# NRF51822.net
KiCad netlist of a schematic drawn in Altium Designer
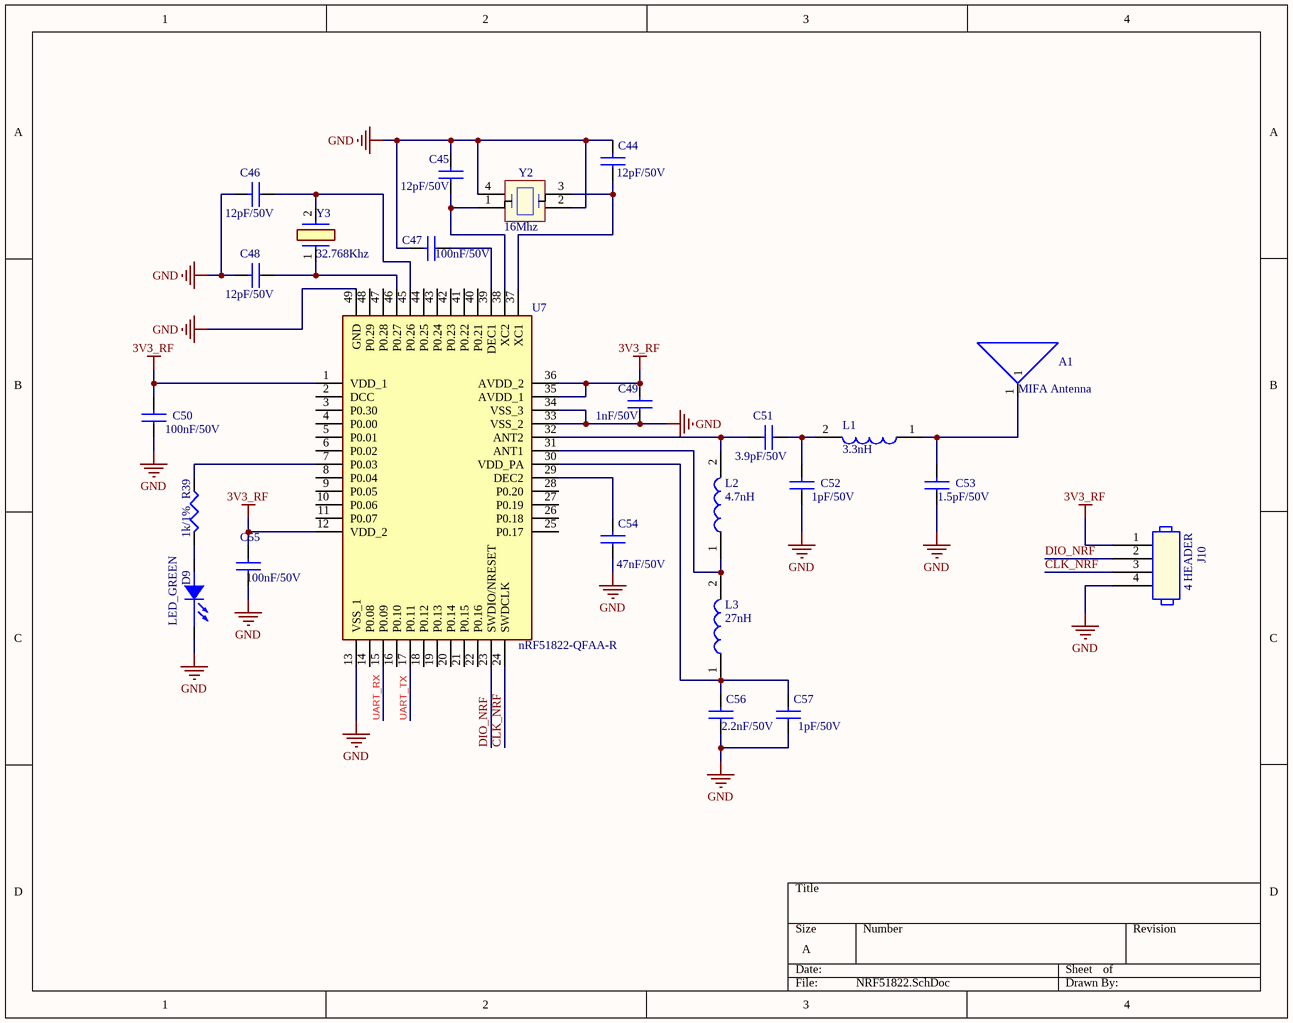
[diagram p0: NRF51822.SchDoc]

(export (version "E")
  (design (tool "Eeschema 10.0.6"))
  (components
    (comp (ref "A1")
      (value "MIFA Antenna")
      (footprint "ANT-2.4GHZ-8.0X1.0MM")
      (description "None")
      (libsource (lib "VESC_DEVICE_Library") (part "Ceramic _ANTENNA"))
    )
    (comp (ref "C44") (value "12pF/50V") (footprint "C0402") (libsource (lib "*") (part "CAP NP")))
    (comp (ref "C45") (value "12pF/50V") (footprint "C0402") (libsource (lib "*") (part "CAP NP")))
    (comp (ref "C46") (value "12pF/50V") (footprint "C0402") (libsource (lib "*") (part "CAP NP")))
    (comp (ref "C47") (value "100nF/50V") (footprint "C0402") (libsource (lib "*") (part "CAP NP")))
    (comp (ref "C48") (value "12pF/50V") (footprint "C0402") (libsource (lib "*") (part "CAP NP")))
    (comp (ref "C49") (value "1nF/50V") (footprint "C0402") (libsource (lib "*") (part "CAP NP")))
    (comp (ref "C50") (value "100nF/50V") (footprint "C0402") (libsource (lib "*") (part "CAP NP")))
    (comp (ref "C51") (value "3.9pF/50V") (footprint "C0402") (libsource (lib "*") (part "CAP NP")))
    (comp (ref "C52") (value "1pF/50V") (footprint "C0402") (libsource (lib "*") (part "CAP NP")))
    (comp (ref "C53") (value "1.5pF/50V") (footprint "C0402") (libsource (lib "*") (part "CAP NP")))
    (comp (ref "C54") (value "47nF/50V") (footprint "C0402") (libsource (lib "*") (part "CAP NP")))
    (comp (ref "C55") (value "100nF/50V") (footprint "C0402") (libsource (lib "*") (part "CAP NP")))
    (comp (ref "C56") (value "2.2nF/50V") (footprint "C0402") (libsource (lib "*") (part "CAP NP")))
    (comp (ref "C57") (value "1pF/50V") (footprint "C0402") (libsource (lib "*") (part "CAP NP")))
    (comp (ref "D9") (value "LED_GREEN") (footprint "LED0603") (libsource (lib "*") (part "LED")))
    (comp (ref "J10") (value "4 HEADER") (footprint "ISP-4P-2_54") (libsource (lib "*") (part "4 HEADER")))
    (comp (ref "L1")
      (value "3.3nH")
      (footprint "LQG15WH0N7B02D")
      (description "Inductor")
      (fields
        (field (name "MANUFACTURER_PART_NUMBER") "LQG15HS4N7C02D")
        (field (name "MOUSER PART NUMBER") "81-LQG15HS4N7C02D")
      )
      (libsource (lib "VESC_DEVICE_Library") (part "LQG15HS4N7C02D"))
    )
    (comp (ref "L2")
      (value "4.7nH")
      (footprint "LQG15WH0N7B02D")
      (description "Inductor")
      (fields
        (field (name "MANUFACTURER_PART_NUMBER") "LQG15HS4N7C02D")
        (field (name "MOUSER PART NUMBER") "81-LQG15HS4N7C02D")
      )
      (libsource (lib "VESC_DEVICE_Library") (part "LQG15HS4N7C02D"))
    )
    (comp (ref "L3")
      (value "27nH")
      (footprint "LQG15WH0N7B02D")
      (description "Inductor")
      (fields
        (field (name "MANUFACTURER_PART_NUMBER") "LQG15HS4N7C02D")
        (field (name "MOUSER PART NUMBER") "81-LQG15HS4N7C02D")
      )
      (libsource (lib "VESC_DEVICE_Library") (part "LQG15HS4N7C02D"))
    )
    (comp (ref "R39") (value "1k/1%") (footprint "R0402") (libsource (lib "*") (part "RESISTOR")))
    (comp (ref "U7")
      (value "nRF51822-QFAA-R")
      (footprint "SamacSys:QFN40P600X600X95-49N-D")
      (description "Integrated Circuit")
      (fields
        (field (name "MOUSER PART NUMBER") "949-NRF51822-QFAA-R")
        (field (name "ARROW PART NUMBER") "NRF51822-QFAA-R")
      )
      (libsource (lib "VESC_DEVICE_Library") (part "nRF51822-QFAA-R"))
    )
    (comp (ref "Y2")
      (value "16Mhz")
      (footprint "Q22FA12800400")
      (description "Crystal or Oscillator")
      (fields (field (name "MANUFACTURER_PART_NUMBER") "Q22FA12800400"))
      (libsource (lib "VESC_DEVICE_Library") (part "Q22FA12800400"))
    )
    (comp (ref "Y3")
      (value "32.768Khz")
      (footprint "ABS0532768KHZ9T")
      (description "Crystal or Oscillator")
      (fields
        (field (name "MANUFACTURER_PART_NUMBER") "ABS05-32.768KHZ-9-T")
        (field (name "MOUSER PART NUMBER") "815-ABS05-32.768K9T")
      )
      (libsource (lib "VESC_DEVICE_Library") (part "ABS05-32.768KHZ-9-T"))
    )
  )
  (nets
    (net (code "1") (name "/CLK_NRF") (class "Default")
      (node (ref "J10") (pin "3") (pinfunction "3_3") (pintype "passive"))
      (node (ref "U7") (pin "24") (pinfunction "SWDCLK_24") (pintype "passive"))
    )
    (net (code "2") (name "/DIO_NRF") (class "Default")
      (node (ref "J10") (pin "2") (pinfunction "2_2") (pintype "passive"))
      (node (ref "U7") (pin "23") (pinfunction "SWDIO/NRESET_23") (pintype "passive"))
    )
    (net (code "3") (name "/UART_RX") (class "Default")
      (node (ref "U7") (pin "15") (pinfunction "P0.09_15") (pintype "passive"))
    )
    (net (code "4") (name "/UART_TX") (class "Default")
      (node (ref "U7") (pin "17") (pinfunction "P0.11_17") (pintype "passive"))
    )
    (net (code "5") (name "3V3_RF") (class "Default")
      (node (ref "C49") (pin "2") (pinfunction "2_2") (pintype "passive"))
      (node (ref "C50") (pin "2") (pinfunction "2_2") (pintype "passive"))
      (node (ref "C55") (pin "2") (pinfunction "2_2") (pintype "passive"))
      (node (ref "J10") (pin "1") (pinfunction "1_1") (pintype "passive"))
      (node (ref "U7") (pin "1") (pinfunction "VDD_1_1") (pintype "passive"))
      (node (ref "U7") (pin "12") (pinfunction "VDD_2_12") (pintype "passive"))
      (node (ref "U7") (pin "35") (pinfunction "AVDD_1_35") (pintype "passive"))
      (node (ref "U7") (pin "36") (pinfunction "AVDD_2_36") (pintype "passive"))
    )
    (net (code "6") (name "GND") (class "Default")
      (node (ref "C44") (pin "2") (pinfunction "2_2") (pintype "passive"))
      (node (ref "C45") (pin "2") (pinfunction "2_2") (pintype "passive"))
      (node (ref "C46") (pin "2") (pinfunction "2_2") (pintype "passive"))
      (node (ref "C47") (pin "2") (pinfunction "2_2") (pintype "passive"))
      (node (ref "C48") (pin "2") (pinfunction "2_2") (pintype "passive"))
      (node (ref "C49") (pin "1") (pinfunction "1_1") (pintype "passive"))
      (node (ref "C50") (pin "1") (pinfunction "1_1") (pintype "passive"))
      (node (ref "C52") (pin "1") (pinfunction "1_1") (pintype "passive"))
      (node (ref "C53") (pin "1") (pinfunction "1_1") (pintype "passive"))
      (node (ref "C54") (pin "1") (pinfunction "1_1") (pintype "passive"))
      (node (ref "C55") (pin "1") (pinfunction "1_1") (pintype "passive"))
      (node (ref "C56") (pin "1") (pinfunction "1_1") (pintype "passive"))
      (node (ref "C57") (pin "1") (pinfunction "1_1") (pintype "passive"))
      (node (ref "D9") (pin "1") (pinfunction "CATHODE_1") (pintype "passive"))
      (node (ref "J10") (pin "4") (pinfunction "4_4") (pintype "passive"))
      (node (ref "U7") (pin "13") (pinfunction "VSS_1_13") (pintype "passive"))
      (node (ref "U7") (pin "33") (pinfunction "VSS_2_33") (pintype "passive"))
      (node (ref "U7") (pin "34") (pinfunction "VSS_3_34") (pintype "passive"))
      (node (ref "U7") (pin "49") (pinfunction "GND_49") (pintype "passive"))
      (node (ref "Y2") (pin "2") (pinfunction "GND_1_2") (pintype "passive"))
      (node (ref "Y2") (pin "4") (pinfunction "GND_2_4") (pintype "passive"))
    )
    (net (code "7") (name "Net-(A1-Pad1)") (class "Default")
      (node (ref "A1") (pin "1") (pinfunction "1_1") (pintype "passive"))
      (node (ref "C53") (pin "2") (pinfunction "2_2") (pintype "passive"))
      (node (ref "L1") (pin "1") (pinfunction "1_1") (pintype "passive"))
    )
    (net (code "8") (name "Net-(C51-Pad1)") (class "Default")
      (node (ref "C51") (pin "1") (pinfunction "1_1") (pintype "passive"))
      (node (ref "C52") (pin "2") (pinfunction "2_2") (pintype "passive"))
      (node (ref "L1") (pin "2") (pinfunction "2_2") (pintype "passive"))
    )
    (net (code "9") (name "Net-(D9-ANODE)") (class "Default")
      (node (ref "D9") (pin "2") (pinfunction "ANODE_2") (pintype "passive"))
      (node (ref "R39") (pin "1") (pinfunction "1_1") (pintype "passive"))
    )
    (net (code "10") (name "Net-(U7-ANT1)") (class "Default")
      (node (ref "L2") (pin "1") (pinfunction "1_1") (pintype "passive"))
      (node (ref "L3") (pin "2") (pinfunction "2_2") (pintype "passive"))
      (node (ref "U7") (pin "31") (pinfunction "ANT1_31") (pintype "passive"))
    )
    (net (code "11") (name "Net-(U7-ANT2)") (class "Default")
      (node (ref "C51") (pin "2") (pinfunction "2_2") (pintype "passive"))
      (node (ref "L2") (pin "2") (pinfunction "2_2") (pintype "passive"))
      (node (ref "U7") (pin "32") (pinfunction "ANT2_32") (pintype "passive"))
    )
    (net (code "12") (name "Net-(U7-DEC1)") (class "Default")
      (node (ref "C47") (pin "1") (pinfunction "1_1") (pintype "passive"))
      (node (ref "U7") (pin "39") (pinfunction "DEC1_39") (pintype "passive"))
    )
    (net (code "13") (name "Net-(U7-DEC2)") (class "Default")
      (node (ref "C54") (pin "2") (pinfunction "2_2") (pintype "passive"))
      (node (ref "U7") (pin "29") (pinfunction "DEC2_29") (pintype "passive"))
    )
    (net (code "14") (name "Net-(U7-P0.03)") (class "Default")
      (node (ref "R39") (pin "2") (pinfunction "2_2") (pintype "passive"))
      (node (ref "U7") (pin "7") (pinfunction "P0.03_7") (pintype "passive"))
    )
    (net (code "15") (name "Net-(U7-P0.26)") (class "Default")
      (node (ref "C46") (pin "1") (pinfunction "1_1") (pintype "passive"))
      (node (ref "U7") (pin "45") (pinfunction "P0.26_45") (pintype "passive"))
      (node (ref "Y3") (pin "2") (pinfunction "2_2") (pintype "passive"))
    )
    (net (code "16") (name "Net-(U7-P0.27)") (class "Default")
      (node (ref "C48") (pin "1") (pinfunction "1_1") (pintype "passive"))
      (node (ref "U7") (pin "46") (pinfunction "P0.27_46") (pintype "passive"))
      (node (ref "Y3") (pin "1") (pinfunction "1_1") (pintype "passive"))
    )
    (net (code "17") (name "Net-(U7-VDD_PA)") (class "Default")
      (node (ref "C56") (pin "2") (pinfunction "2_2") (pintype "passive"))
      (node (ref "C57") (pin "2") (pinfunction "2_2") (pintype "passive"))
      (node (ref "L3") (pin "1") (pinfunction "1_1") (pintype "passive"))
      (node (ref "U7") (pin "30") (pinfunction "VDD_PA_30") (pintype "passive"))
    )
    (net (code "18") (name "Net-(U7-XC1)") (class "Default")
      (node (ref "C44") (pin "1") (pinfunction "1_1") (pintype "passive"))
      (node (ref "U7") (pin "37") (pinfunction "XC1_37") (pintype "passive"))
      (node (ref "Y2") (pin "3") (pinfunction "CRYSTAL_2_3") (pintype "passive"))
    )
    (net (code "19") (name "Net-(U7-XC2)") (class "Default")
      (node (ref "C45") (pin "1") (pinfunction "1_1") (pintype "passive"))
      (node (ref "U7") (pin "38") (pinfunction "XC2_38") (pintype "passive"))
      (node (ref "Y2") (pin "1") (pinfunction "CRYSTAL_1_1") (pintype "passive"))
    )
    (net (code "20") (name "unconnected-(U7-DCC-Pad2)") (class "Default")
      (node (ref "U7") (pin "2") (pinfunction "DCC_2") (pintype "passive"))
    )
    (net (code "21") (name "unconnected-(U7-P0.00-Pad4)") (class "Default")
      (node (ref "U7") (pin "4") (pinfunction "P0.00_4") (pintype "passive"))
    )
    (net (code "22") (name "unconnected-(U7-P0.01-Pad5)") (class "Default")
      (node (ref "U7") (pin "5") (pinfunction "P0.01_5") (pintype "passive"))
    )
    (net (code "23") (name "unconnected-(U7-P0.02-Pad6)") (class "Default")
      (node (ref "U7") (pin "6") (pinfunction "P0.02_6") (pintype "passive"))
    )
    (net (code "24") (name "unconnected-(U7-P0.04-Pad8)") (class "Default")
      (node (ref "U7") (pin "8") (pinfunction "P0.04_8") (pintype "passive"))
    )
    (net (code "25") (name "unconnected-(U7-P0.05-Pad9)") (class "Default")
      (node (ref "U7") (pin "9") (pinfunction "P0.05_9") (pintype "passive"))
    )
    (net (code "26") (name "unconnected-(U7-P0.06-Pad10)") (class "Default")
      (node (ref "U7") (pin "10") (pinfunction "P0.06_10") (pintype "passive"))
    )
    (net (code "27") (name "unconnected-(U7-P0.07-Pad11)") (class "Default")
      (node (ref "U7") (pin "11") (pinfunction "P0.07_11") (pintype "passive"))
    )
    (net (code "28") (name "unconnected-(U7-P0.08-Pad14)") (class "Default")
      (node (ref "U7") (pin "14") (pinfunction "P0.08_14") (pintype "passive"))
    )
    (net (code "29") (name "unconnected-(U7-P0.10-Pad16)") (class "Default")
      (node (ref "U7") (pin "16") (pinfunction "P0.10_16") (pintype "passive"))
    )
    (net (code "30") (name "unconnected-(U7-P0.12-Pad18)") (class "Default")
      (node (ref "U7") (pin "18") (pinfunction "P0.12_18") (pintype "passive"))
    )
    (net (code "31") (name "unconnected-(U7-P0.13-Pad19)") (class "Default")
      (node (ref "U7") (pin "19") (pinfunction "P0.13_19") (pintype "passive"))
    )
    (net (code "32") (name "unconnected-(U7-P0.14-Pad20)") (class "Default")
      (node (ref "U7") (pin "20") (pinfunction "P0.14_20") (pintype "passive"))
    )
    (net (code "33") (name "unconnected-(U7-P0.15-Pad21)") (class "Default")
      (node (ref "U7") (pin "21") (pinfunction "P0.15_21") (pintype "passive"))
    )
    (net (code "34") (name "unconnected-(U7-P0.16-Pad22)") (class "Default")
      (node (ref "U7") (pin "22") (pinfunction "P0.16_22") (pintype "passive"))
    )
    (net (code "35") (name "unconnected-(U7-P0.17-Pad25)") (class "Default")
      (node (ref "U7") (pin "25") (pinfunction "P0.17_25") (pintype "passive"))
    )
    (net (code "36") (name "unconnected-(U7-P0.18-Pad26)") (class "Default")
      (node (ref "U7") (pin "26") (pinfunction "P0.18_26") (pintype "passive"))
    )
    (net (code "37") (name "unconnected-(U7-P0.19-Pad27)") (class "Default")
      (node (ref "U7") (pin "27") (pinfunction "P0.19_27") (pintype "passive"))
    )
    (net (code "38") (name "unconnected-(U7-P0.20-Pad28)") (class "Default")
      (node (ref "U7") (pin "28") (pinfunction "P0.20_28") (pintype "passive"))
    )
    (net (code "39") (name "unconnected-(U7-P0.21-Pad40)") (class "Default")
      (node (ref "U7") (pin "40") (pinfunction "P0.21_40") (pintype "passive"))
    )
    (net (code "40") (name "unconnected-(U7-P0.22-Pad41)") (class "Default")
      (node (ref "U7") (pin "41") (pinfunction "P0.22_41") (pintype "passive"))
    )
    (net (code "41") (name "unconnected-(U7-P0.23-Pad42)") (class "Default")
      (node (ref "U7") (pin "42") (pinfunction "P0.23_42") (pintype "passive"))
    )
    (net (code "42") (name "unconnected-(U7-P0.24-Pad43)") (class "Default")
      (node (ref "U7") (pin "43") (pinfunction "P0.24_43") (pintype "passive"))
    )
    (net (code "43") (name "unconnected-(U7-P0.25-Pad44)") (class "Default")
      (node (ref "U7") (pin "44") (pinfunction "P0.25_44") (pintype "passive"))
    )
    (net (code "44") (name "unconnected-(U7-P0.28-Pad47)") (class "Default")
      (node (ref "U7") (pin "47") (pinfunction "P0.28_47") (pintype "passive"))
    )
    (net (code "45") (name "unconnected-(U7-P0.29-Pad48)") (class "Default")
      (node (ref "U7") (pin "48") (pinfunction "P0.29_48") (pintype "passive"))
    )
    (net (code "46") (name "unconnected-(U7-P0.30-Pad3)") (class "Default")
      (node (ref "U7") (pin "3") (pinfunction "P0.30_3") (pintype "passive"))
    )
  )
)
